# S7G2_IO_Test_Platform.net
KiCad netlist of a schematic drawn in EAGLE
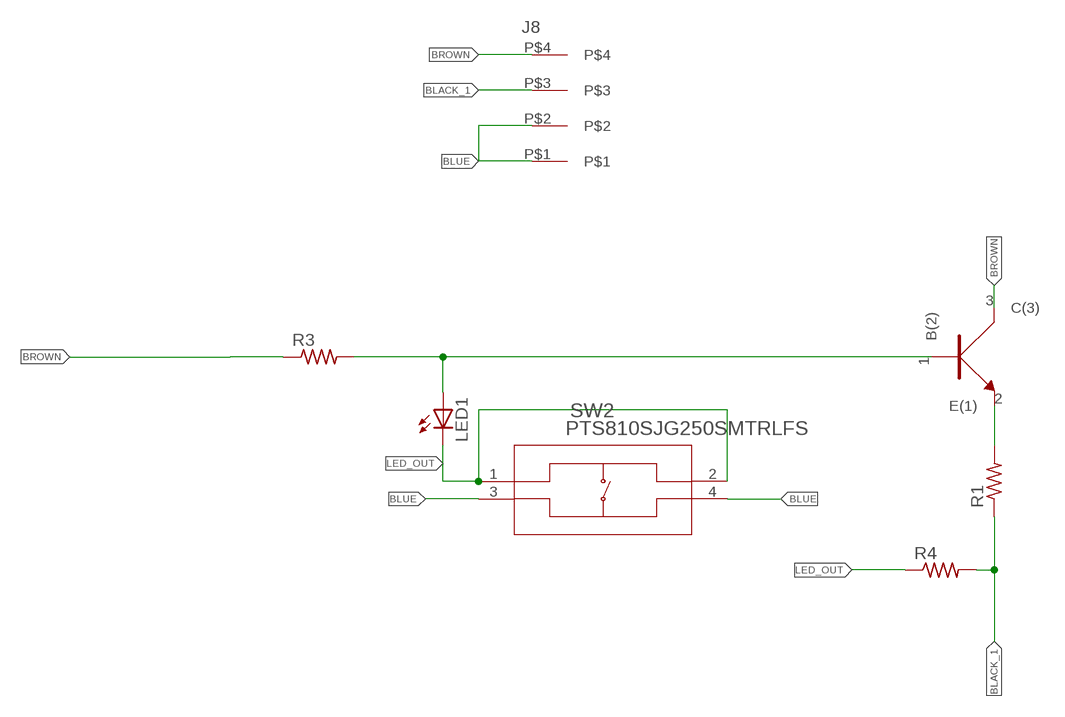
[diagram p0: schematic, sheet 1]

(export (version "E")
  (design (tool "Eeschema 10.0.6"))
  (components
    (comp (ref "J8")
      (value "4-pos")
      (footprint "eagle-import:1X4_3.81MM_PITCH")
      (fields (field (name "PARTNO") "691322310004"))
      (libsource (lib "eagle-import") (part "3.81MM_1_X_4_RT_ANGLE_PLUG_HEADER"))
    )
    (comp (ref "LED1")
      (value "Green")
      (footprint "eagle-import:0805")
      (fields (field (name "PARTNO") "LG R971-KN-1"))
      (libsource (lib "eagle-import") (part "LED_0805_GREEN"))
    )
    (comp (ref "R1")
      (value "R_0805")
      (footprint "eagle-import:0805")
      (libsource (lib "eagle-import") (part "R_0805"))
    )
    (comp (ref "R3")
      (value "R_0805")
      (footprint "eagle-import:0805")
      (libsource (lib "eagle-import") (part "R_0805"))
    )
    (comp (ref "R4")
      (value "R_0805")
      (footprint "eagle-import:0805")
      (libsource (lib "eagle-import") (part "R_0805"))
    )
    (comp (ref "SW2")
      (value "PTS810SJG250SMTRLFS")
      (footprint "eagle-import:PTS810")
      (fields (field (name "COPYRIGHT") "Copyright (C) 2018 Accelerated Designs. All rights reserved"))
      (libsource (lib "eagle-import") (part "PTS810SJG250SMTRLFS"))
    )
    (comp (ref "U1")
      (value "NPN")
      (footprint "eagle-import:SOT323")
      (fields (field (name "PARTNO") "BC846BW_NPN"))
      (libsource (lib "eagle-import") (part "BC846BW"))
    )
  )
  (nets
    (net (code "1") (name "BLACK_1") (class "Default")
      (node (ref "J8") (pin "P$3") (pinfunction "P$3_P$3") (pintype "bidirectional"))
      (node (ref "R1") (pin "1") (pinfunction "1_1") (pintype "passive"))
      (node (ref "R4") (pin "2") (pinfunction "2_2") (pintype "passive"))
    )
    (net (code "2") (name "BLUE") (class "Default")
      (node (ref "J8") (pin "P$1") (pinfunction "P$1_P$1") (pintype "bidirectional"))
      (node (ref "J8") (pin "P$2") (pinfunction "P$2_P$2") (pintype "bidirectional"))
      (node (ref "SW2") (pin "3") (pinfunction "3_3") (pintype "passive"))
      (node (ref "SW2") (pin "4") (pinfunction "4_4") (pintype "passive"))
    )
    (net (code "3") (name "BROWN") (class "Default")
      (node (ref "J8") (pin "P$4") (pinfunction "P$4_P$4") (pintype "bidirectional"))
      (node (ref "R3") (pin "1") (pinfunction "1_1") (pintype "passive"))
      (node (ref "U1") (pin "3") (pinfunction "C(3)_3") (pintype "input"))
    )
    (net (code "4") (name "LED_OUT") (class "Default")
      (node (ref "LED1") (pin "2") (pinfunction "C_2") (pintype "passive"))
      (node (ref "R4") (pin "1") (pinfunction "1_1") (pintype "passive"))
      (node (ref "SW2") (pin "1") (pinfunction "1_1") (pintype "passive"))
      (node (ref "SW2") (pin "2") (pinfunction "2_2") (pintype "passive"))
    )
    (net (code "5") (name "Net-(LED1-A)") (class "Default")
      (node (ref "LED1") (pin "1") (pinfunction "A_1") (pintype "passive"))
      (node (ref "R3") (pin "2") (pinfunction "2_2") (pintype "passive"))
      (node (ref "U1") (pin "1") (pinfunction "B(2)_1") (pintype "input"))
    )
    (net (code "6") (name "Net-(U1-E(1))") (class "Default")
      (node (ref "R1") (pin "2") (pinfunction "2_2") (pintype "passive"))
      (node (ref "U1") (pin "2") (pinfunction "E(1)_2") (pintype "output"))
    )
  )
)
